# 6coils.net
KiCad netlist of a schematic drawn in EasyEDA
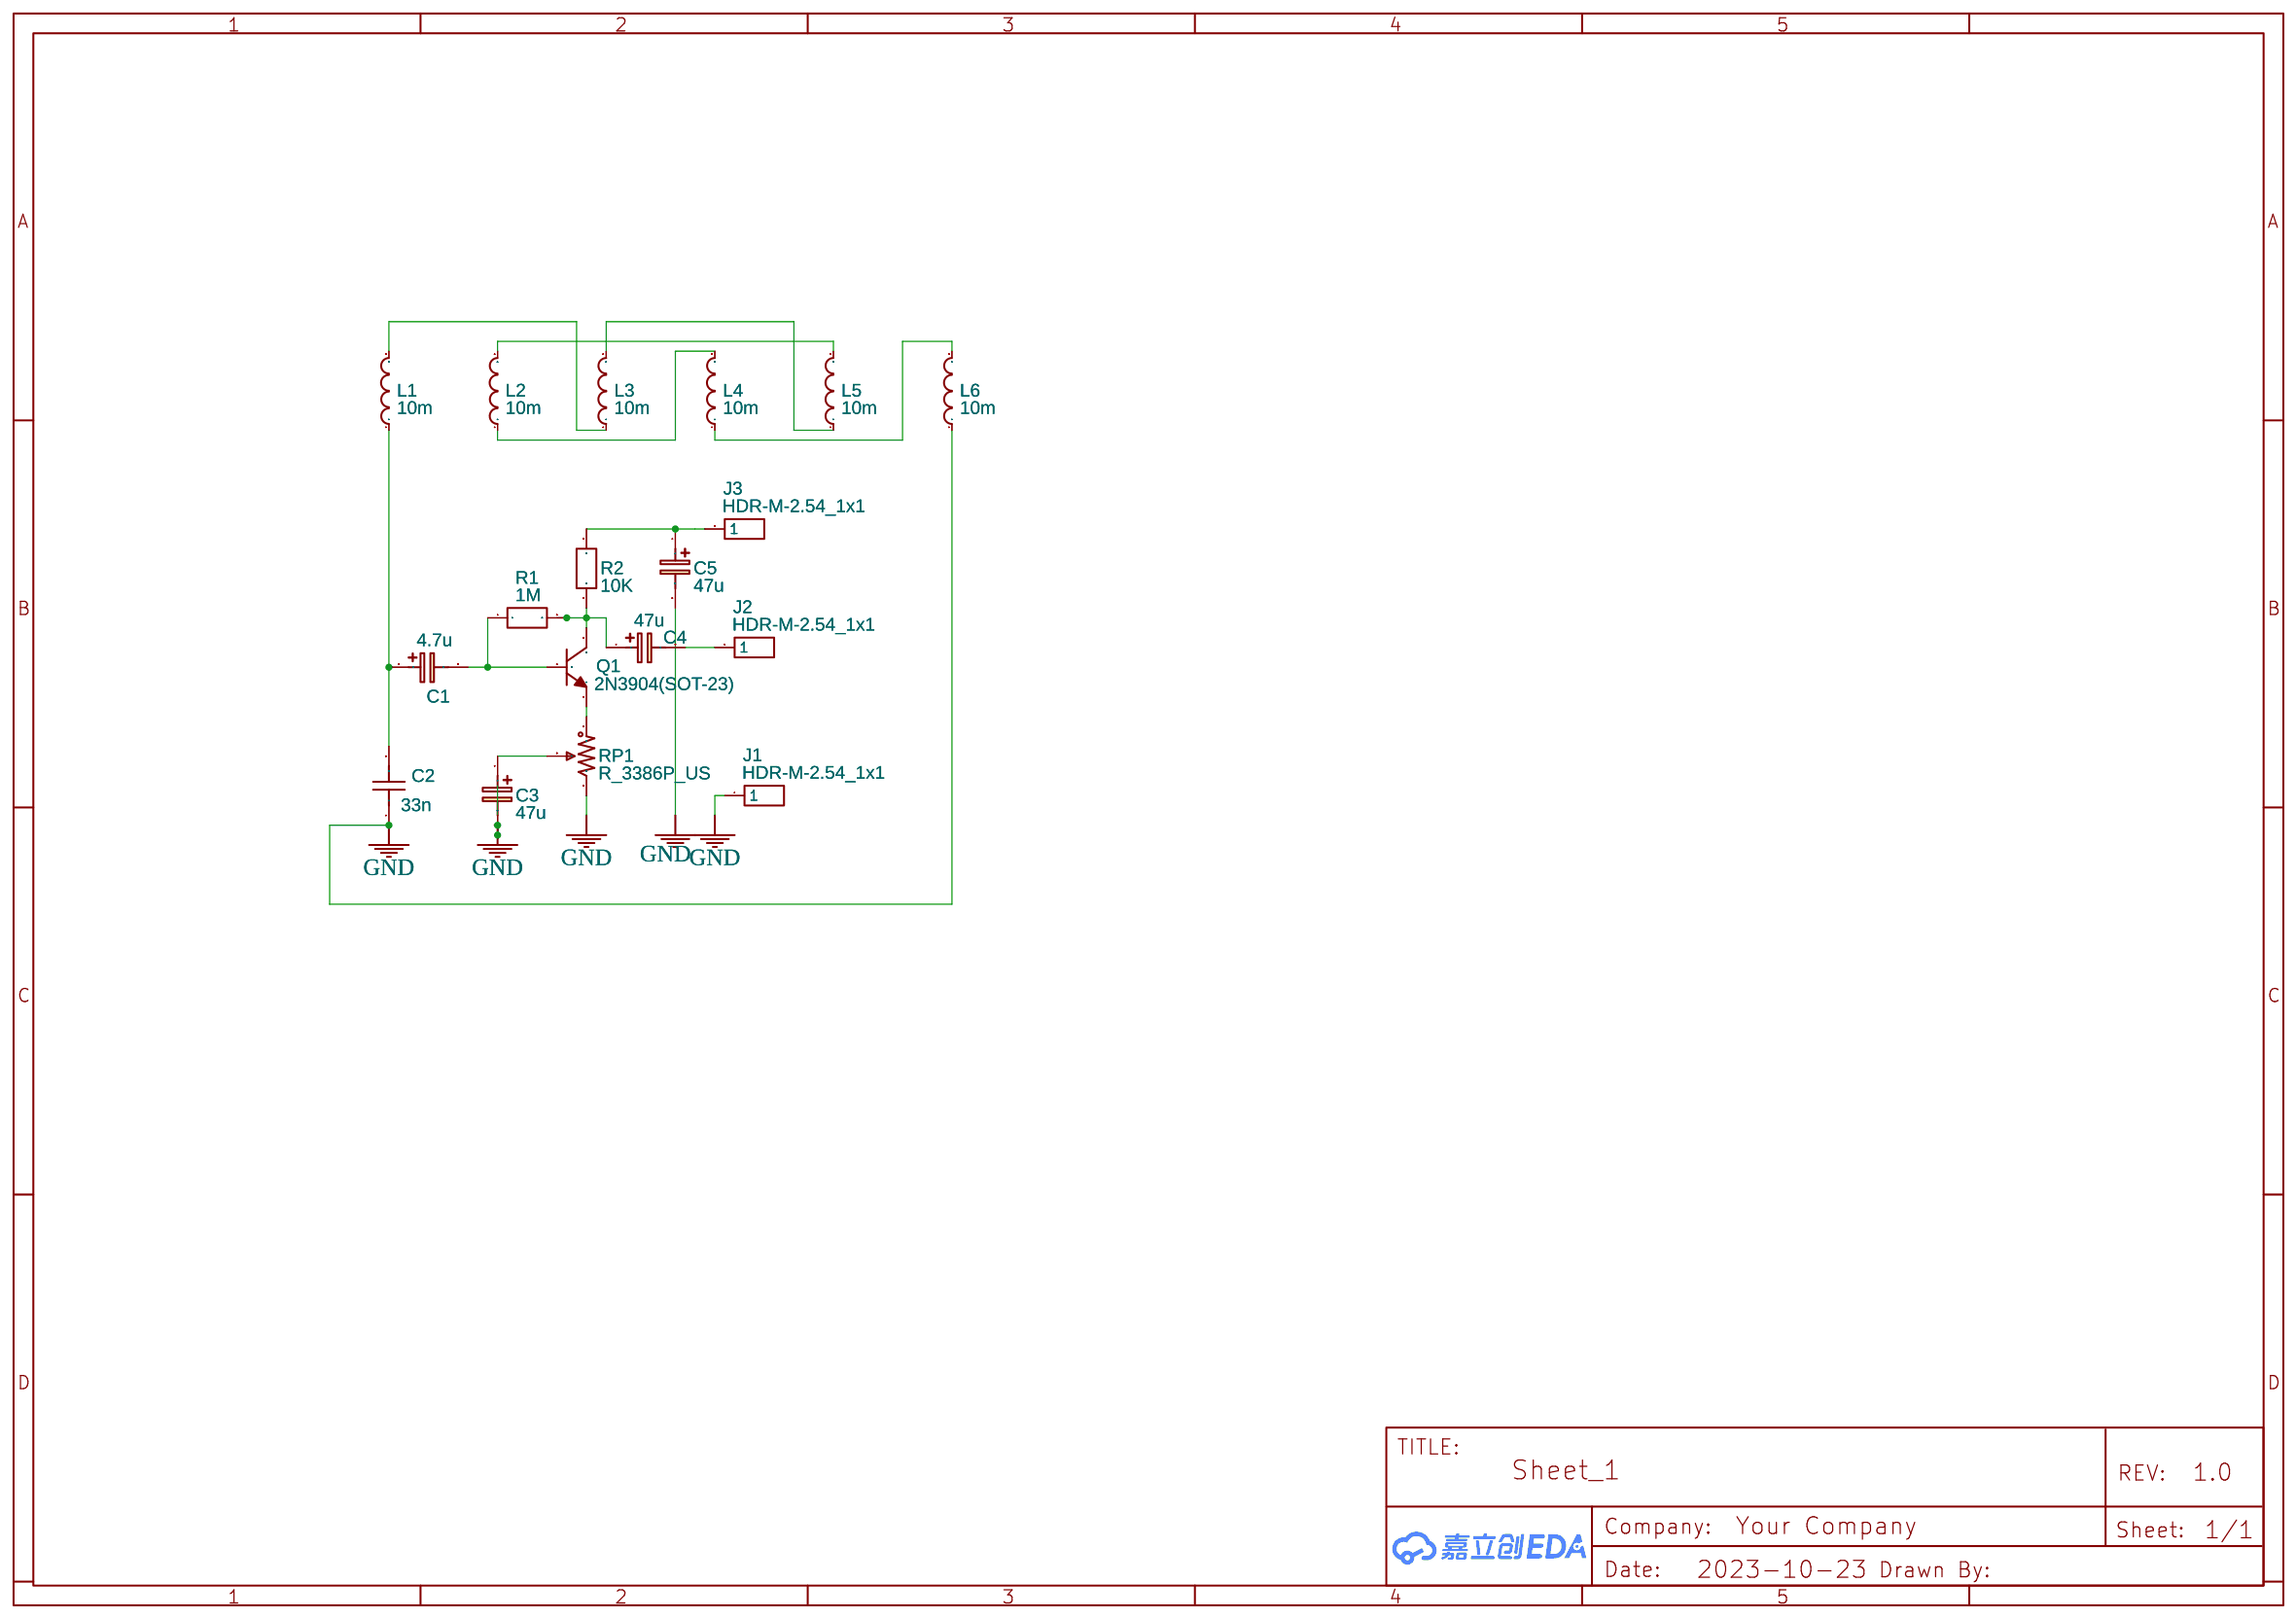
[diagram p0: schematic sheet]

(export (version "E")
  (design (tool "Eeschema 10.0.6"))
  (components
    (comp (ref "C1") (value "4.7u") (libsource (lib "") (part "C_Tan_SMD_A_EU_3")))
    (comp (ref "C2") (value "33n") (libsource (lib "") (part "C_0603_US")))
    (comp (ref "C3") (value "47u") (libsource (lib "") (part "C_Tan_SMD_A_EU_2")))
    (comp (ref "C4") (value "47u") (libsource (lib "") (part "C_Tan_SMD_A_EU")))
    (comp (ref "C5") (value "47u") (libsource (lib "") (part "C_Tan_SMD_A_EU_1")))
    (comp (ref "J1")
      (value "HDR-M-2.54_1x1")
      (fields (field (name "BOM_Supplier Part") "C81276"))
      (libsource (lib "") (part "HDR-M-2.54_1x1"))
    )
    (comp (ref "J2")
      (value "HDR-M-2.54_1x1")
      (fields (field (name "BOM_Supplier Part") "C81276"))
      (libsource (lib "") (part "HDR-M-2.54_1x1"))
    )
    (comp (ref "J3")
      (value "HDR-M-2.54_1x1")
      (fields (field (name "BOM_Supplier Part") "C81276"))
      (libsource (lib "") (part "HDR-M-2.54_1x1"))
    )
    (comp (ref "L1") (value "10m") (libsource (lib "") (part "L0603_US")))
    (comp (ref "L2") (value "10m") (libsource (lib "") (part "L0603_US")))
    (comp (ref "L3") (value "10m") (libsource (lib "") (part "L0603_US")))
    (comp (ref "L4") (value "10m") (libsource (lib "") (part "L0603_US")))
    (comp (ref "L5") (value "10m") (libsource (lib "") (part "L0603_US")))
    (comp (ref "L6") (value "10m") (libsource (lib "") (part "L0603_US")))
    (comp (ref "Q1")
      (value "2N3904(SOT-23)")
      (fields
        (field (name "BOM_Manufacturer Part") "2n3904S-RTK/PS")
        (field (name "BOM_Supplier Part") "C18536")
      )
      (libsource (lib "") (part "2N3904(SOT-23)"))
    )
    (comp (ref "R1") (value "1M") (libsource (lib "") (part "R_0603_EU")))
    (comp (ref "R2") (value "10K") (libsource (lib "") (part "R_0603_EU_1")))
    (comp (ref "RP1") (value "R_3386P_US") (libsource (lib "") (part "R_3386P_US")))
  )
  (nets
    (net (code "1") (name "GND") (class "Default")
      (node (ref "C2") (pin "1") (pinfunction "1_1") (pintype "unspecified"))
      (node (ref "C3") (pin "2") (pinfunction "2_2") (pintype "unspecified"))
      (node (ref "C5") (pin "2") (pinfunction "2_2") (pintype "unspecified"))
      (node (ref "J1") (pin "1") (pinfunction "1_1") (pintype "input"))
      (node (ref "L6") (pin "1") (pinfunction "1_1") (pintype "unspecified"))
      (node (ref "RP1") (pin "3") (pinfunction "3_3") (pintype "unspecified"))
    )
    (net (code "2") (name "Net-(C1-Pad1)") (class "Default")
      (node (ref "C1") (pin "1") (pinfunction "1_1") (pintype "unspecified"))
      (node (ref "C2") (pin "2") (pinfunction "2_2") (pintype "unspecified"))
      (node (ref "L1") (pin "1") (pinfunction "1_1") (pintype "unspecified"))
    )
    (net (code "3") (name "Net-(C3-Pad1)") (class "Default")
      (node (ref "C3") (pin "1") (pinfunction "1_1") (pintype "unspecified"))
      (node (ref "RP1") (pin "2") (pinfunction "2_2") (pintype "unspecified"))
    )
    (net (code "4") (name "Net-(C4-Pad2)") (class "Default")
      (node (ref "C4") (pin "2") (pinfunction "2_2") (pintype "unspecified"))
      (node (ref "J2") (pin "1") (pinfunction "1_1") (pintype "input"))
    )
    (net (code "5") (name "Net-(C5-Pad1)") (class "Default")
      (node (ref "C5") (pin "1") (pinfunction "1_1") (pintype "unspecified"))
      (node (ref "J3") (pin "1") (pinfunction "1_1") (pintype "input"))
      (node (ref "R2") (pin "2") (pinfunction "2_2") (pintype "unspecified"))
    )
    (net (code "6") (name "Net-(L1-Pad2)") (class "Default")
      (node (ref "L1") (pin "2") (pinfunction "2_2") (pintype "unspecified"))
      (node (ref "L3") (pin "1") (pinfunction "1_1") (pintype "unspecified"))
    )
    (net (code "7") (name "Net-(L2-Pad1)") (class "Default")
      (node (ref "L2") (pin "1") (pinfunction "1_1") (pintype "unspecified"))
      (node (ref "L4") (pin "2") (pinfunction "2_2") (pintype "unspecified"))
    )
    (net (code "8") (name "Net-(L2-Pad2)") (class "Default")
      (node (ref "L2") (pin "2") (pinfunction "2_2") (pintype "unspecified"))
      (node (ref "L5") (pin "2") (pinfunction "2_2") (pintype "unspecified"))
    )
    (net (code "9") (name "Net-(L3-Pad2)") (class "Default")
      (node (ref "L3") (pin "2") (pinfunction "2_2") (pintype "unspecified"))
      (node (ref "L5") (pin "1") (pinfunction "1_1") (pintype "unspecified"))
    )
    (net (code "10") (name "Net-(L4-Pad1)") (class "Default")
      (node (ref "L4") (pin "1") (pinfunction "1_1") (pintype "unspecified"))
      (node (ref "L6") (pin "2") (pinfunction "2_2") (pintype "unspecified"))
    )
    (net (code "11") (name "Net-(Q1-B)") (class "Default")
      (node (ref "C1") (pin "2") (pinfunction "2_2") (pintype "unspecified"))
      (node (ref "Q1") (pin "2") (pinfunction "B_2") (pintype "input"))
      (node (ref "R1") (pin "1") (pinfunction "1_1") (pintype "unspecified"))
    )
    (net (code "12") (name "Net-(Q1-C)") (class "Default")
      (node (ref "C4") (pin "1") (pinfunction "1_1") (pintype "unspecified"))
      (node (ref "Q1") (pin "3") (pinfunction "C_3") (pintype "input"))
      (node (ref "R1") (pin "2") (pinfunction "2_2") (pintype "unspecified"))
      (node (ref "R2") (pin "1") (pinfunction "1_1") (pintype "unspecified"))
    )
    (net (code "13") (name "Net-(Q1-E)") (class "Default")
      (node (ref "Q1") (pin "1") (pinfunction "E_1") (pintype "input"))
      (node (ref "RP1") (pin "1") (pinfunction "1_1") (pintype "unspecified"))
    )
  )
)
